# SparkFun_USB_LiPolyCharger_SingleCell.net
KiCad netlist of a schematic drawn in EAGLE
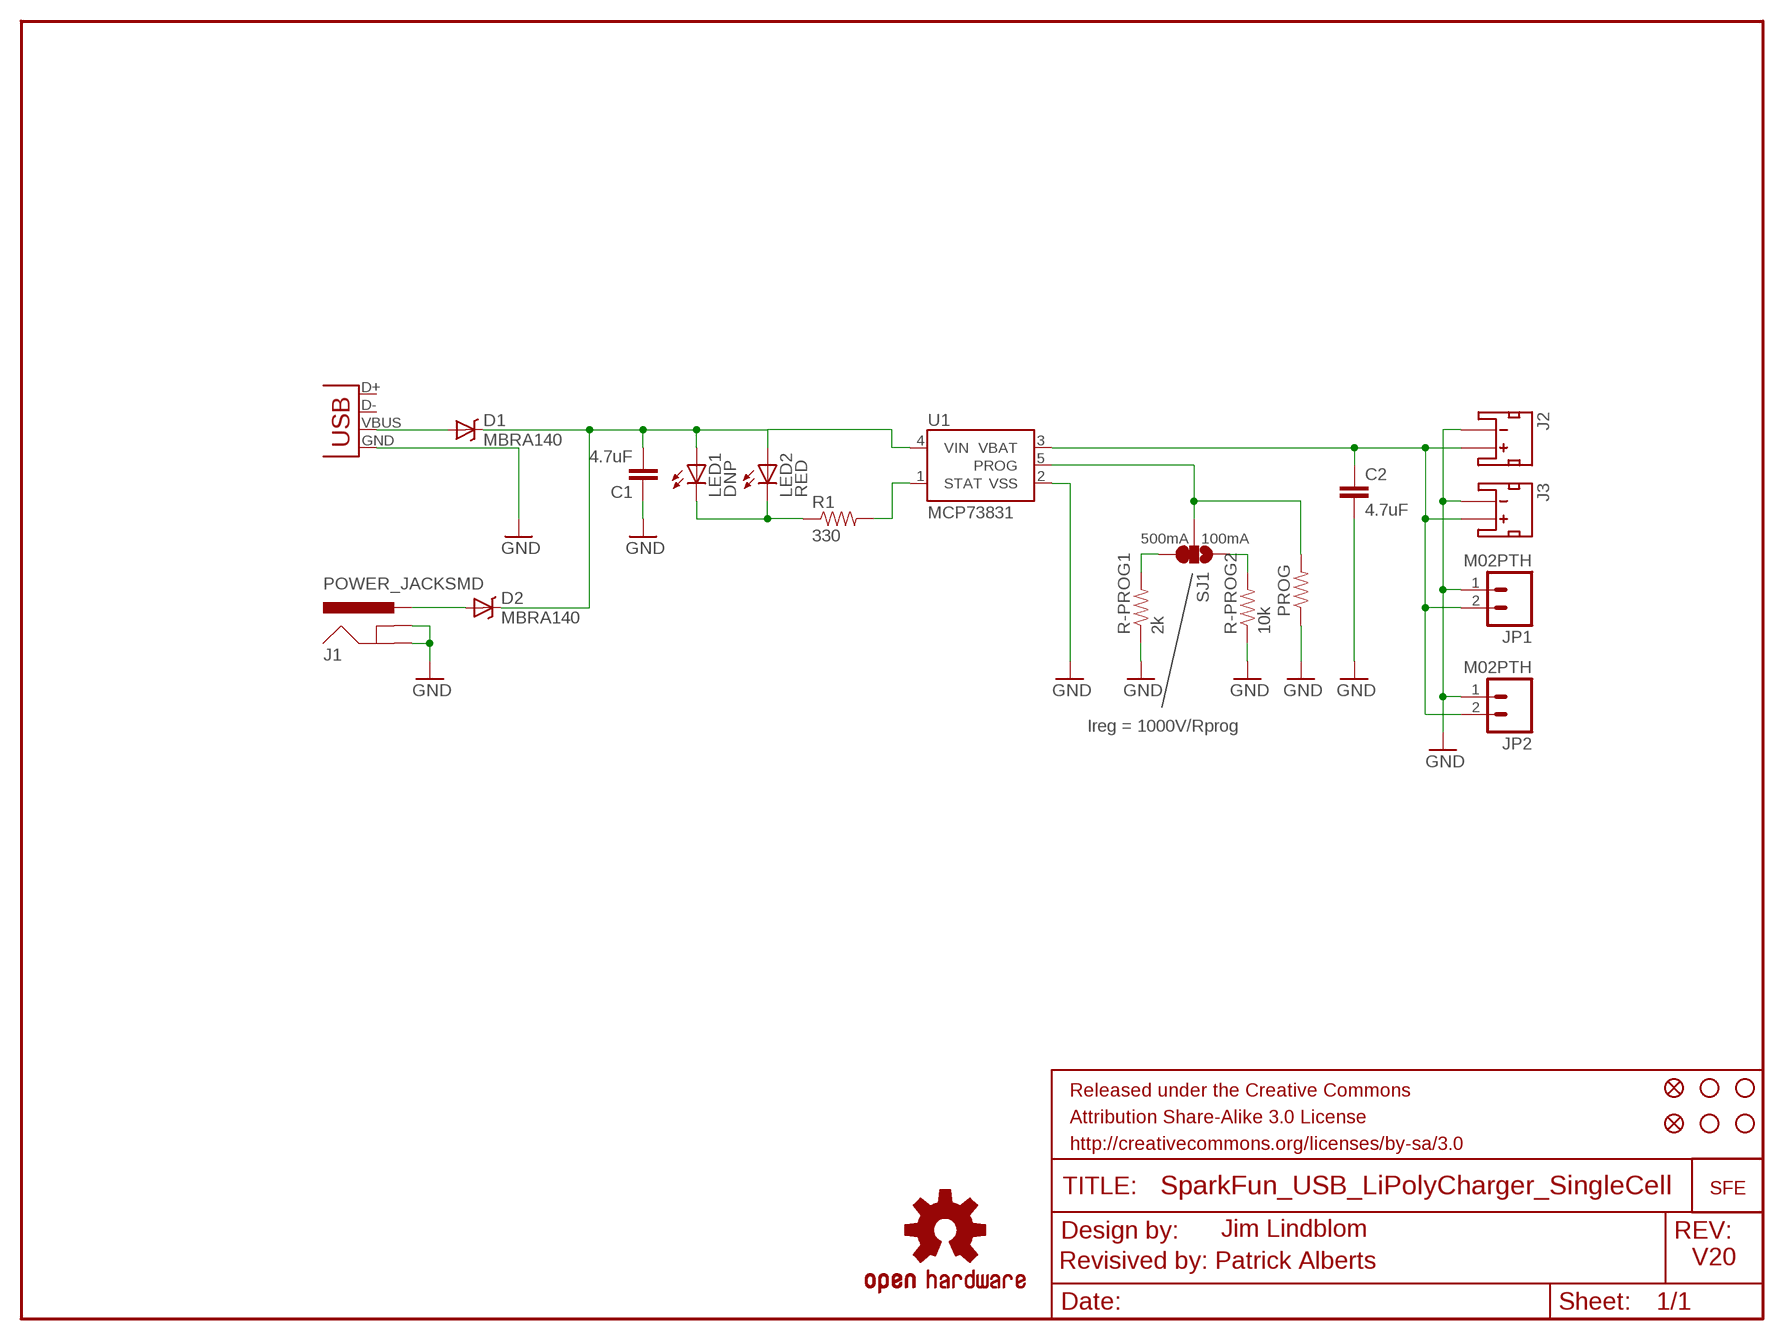
[diagram p0: schematic, sheet 1]

(export (version "E")
  (design (tool "Eeschema 10.0.6"))
  (components
    (comp (ref "C1")
      (value "4.7uF")
      (footprint "eagle-import:0603-CAP")
      (libsource (lib "eagle-import") (part "4.7UF-6.3V-10%(0603)0603"))
    )
    (comp (ref "C2")
      (value "4.7uF")
      (footprint "eagle-import:0603-CAP")
      (libsource (lib "eagle-import") (part "4.7UF-6.3V-10%(0603)0603"))
    )
    (comp (ref "D1")
      (value "MBRA140")
      (footprint "eagle-import:SMA-DIODE")
      (libsource (lib "eagle-import") (part "MBRA140"))
    )
    (comp (ref "D2")
      (value "MBRA140")
      (footprint "eagle-import:SMA-DIODE")
      (libsource (lib "eagle-import") (part "MBRA140"))
    )
    (comp (ref "FRAME1")
      (value "FRAME-LETTER")
      (footprint "eagle-import:CREATIVE_COMMONS")
      (libsource (lib "eagle-import") (part "FRAME-LETTER"))
    )
    (comp (ref "J1")
      (value "POWER_JACKSMD")
      (footprint "eagle-import:POWER_JACK_SMD")
      (libsource (lib "eagle-import") (part "POWER_JACKSMD"))
    )
    (comp (ref "J2")
      (value "JST_2MM_MALE")
      (footprint "eagle-import:JST-2-SMD")
      (libsource (lib "eagle-import") (part "JST_2MM_MALE"))
    )
    (comp (ref "J3")
      (value "JST_2MM_MALE")
      (footprint "eagle-import:JST-2-SMD")
      (libsource (lib "eagle-import") (part "JST_2MM_MALE"))
    )
    (comp (ref "JP1")
      (value "M02PTH")
      (footprint "eagle-import:1X02")
      (libsource (lib "eagle-import") (part "M02PTH"))
    )
    (comp (ref "JP2")
      (value "M02PTH")
      (footprint "eagle-import:1X02")
      (libsource (lib "eagle-import") (part "M02PTH"))
    )
    (comp (ref "JP7")
      (value "STAND-OFF")
      (footprint "eagle-import:STAND-OFF")
      (libsource (lib "eagle-import") (part "STAND-OFF"))
    )
    (comp (ref "JP8")
      (value "STAND-OFF")
      (footprint "eagle-import:STAND-OFF")
      (libsource (lib "eagle-import") (part "STAND-OFF"))
    )
    (comp (ref "JP9")
      (value "STAND-OFF")
      (footprint "eagle-import:STAND-OFF")
      (libsource (lib "eagle-import") (part "STAND-OFF"))
    )
    (comp (ref "JP10")
      (value "STAND-OFF")
      (footprint "eagle-import:STAND-OFF")
      (libsource (lib "eagle-import") (part "STAND-OFF"))
    )
    (comp (ref "JP11")
      (value "LOGO-SFENEW")
      (footprint "eagle-import:SFE-NEW-WEBLOGO")
      (libsource (lib "eagle-import") (part "LOGO-SFENEW"))
    )
    (comp (ref "JP12")
      (value "FIDUCIAL1X2")
      (footprint "eagle-import:FIDUCIAL-1X2")
      (libsource (lib "eagle-import") (part "FIDUCIAL1X2"))
    )
    (comp (ref "JP13")
      (value "FIDUCIAL1X2")
      (footprint "eagle-import:FIDUCIAL-1X2")
      (libsource (lib "eagle-import") (part "FIDUCIAL1X2"))
    )
    (comp (ref "LED1")
      (value "DNP")
      (footprint "eagle-import:LED3MM")
      (libsource (lib "eagle-import") (part "LED3MM"))
    )
    (comp (ref "LED2")
      (value "RED")
      (footprint "eagle-import:LED-0603")
      (libsource (lib "eagle-import") (part "LED-RED0603"))
    )
    (comp (ref "LOGO1")
      (value "OSHW-LOGOS")
      (footprint "eagle-import:OSHW-LOGO-S")
      (libsource (lib "eagle-import") (part "OSHW-LOGOS"))
    )
    (comp (ref "PROG")
      (value "RESISTORAXIAL-0.3")
      (footprint "eagle-import:AXIAL-0.3")
      (libsource (lib "eagle-import") (part "RESISTORAXIAL-0.3"))
    )
    (comp (ref "R-PROG1")
      (value "2k")
      (footprint "eagle-import:0603-RES")
      (libsource (lib "eagle-import") (part "2.0KOHM1/10W5%(0603)"))
    )
    (comp (ref "R-PROG2")
      (value "10k")
      (footprint "eagle-import:0603-RES")
      (libsource (lib "eagle-import") (part "10KOHM1/10W1%(0603)0603"))
    )
    (comp (ref "R1")
      (value "330")
      (footprint "eagle-import:0603-RES")
      (libsource (lib "eagle-import") (part "330OHM1/10W1%(0603)"))
    )
    (comp (ref "SJ1")
      (value "SOLDERJUMPER_2WAYS")
      (footprint "eagle-import:SJ_3")
      (libsource (lib "eagle-import") (part "SOLDERJUMPER_2WAYS"))
    )
    (comp (ref "U1")
      (value "MCP73831")
      (footprint "eagle-import:SOT23-5")
      (libsource (lib "eagle-import") (part "MCP73831"))
    )
    (comp (ref "X1")
      (value "USBSMD")
      (footprint "eagle-import:USB-MINIB")
      (libsource (lib "eagle-import") (part "USBSMD"))
    )
  )
  (nets
    (net (code "1") (name "GND") (class "Default")
      (node (ref "C1") (pin "1") (pinfunction "1_1") (pintype "passive"))
      (node (ref "C2") (pin "2") (pinfunction "2_2") (pintype "passive"))
      (node (ref "J1") (pin "GND") (pinfunction "GNDBREAK_GND") (pintype "bidirectional"))
      (node (ref "J1") (pin "P$4") (pinfunction "GND_P$4") (pintype "bidirectional"))
      (node (ref "J2") (pin "1") (pinfunction "-_1") (pintype "bidirectional"))
      (node (ref "J3") (pin "1") (pinfunction "-_1") (pintype "bidirectional"))
      (node (ref "JP1") (pin "1") (pinfunction "1_1") (pintype "passive"))
      (node (ref "JP2") (pin "1") (pinfunction "1_1") (pintype "passive"))
      (node (ref "PROG") (pin "P$1") (pinfunction "1_P$1") (pintype "passive"))
      (node (ref "R-PROG1") (pin "1") (pinfunction "1_1") (pintype "passive"))
      (node (ref "R-PROG2") (pin "1") (pinfunction "1_1") (pintype "passive"))
      (node (ref "U1") (pin "2") (pinfunction "VSS_2") (pintype "power_in"))
      (node (ref "X1") (pin "GND") (pinfunction "GND_GND") (pintype "bidirectional"))
    )
    (net (code "2") (name "Net-(D1-PadA)") (class "Default")
      (node (ref "D1") (pin "A") (pinfunction "A_A") (pintype "passive"))
      (node (ref "X1") (pin "VBUS") (pinfunction "VBUS_VBUS") (pintype "bidirectional"))
    )
    (net (code "3") (name "Net-(J1-PWR)") (class "Default")
      (node (ref "D2") (pin "A") (pinfunction "A_A") (pintype "passive"))
      (node (ref "J1") (pin "VIN0") (pinfunction "PWR_VIN0") (pintype "bidirectional"))
    )
    (net (code "4") (name "Net-(J2-+)") (class "Default")
      (node (ref "C2") (pin "1") (pinfunction "1_1") (pintype "passive"))
      (node (ref "J2") (pin "2") (pinfunction "+_2") (pintype "bidirectional"))
      (node (ref "J3") (pin "2") (pinfunction "+_2") (pintype "bidirectional"))
      (node (ref "JP1") (pin "2") (pinfunction "2_2") (pintype "passive"))
      (node (ref "JP2") (pin "2") (pinfunction "2_2") (pintype "passive"))
      (node (ref "U1") (pin "3") (pinfunction "VBAT_3") (pintype "power_in"))
    )
    (net (code "5") (name "Net-(LED1-C)") (class "Default")
      (node (ref "LED1") (pin "K") (pinfunction "C_K") (pintype "passive"))
      (node (ref "LED2") (pin "C") (pinfunction "C_C") (pintype "passive"))
      (node (ref "R1") (pin "1") (pinfunction "1_1") (pintype "passive"))
    )
    (net (code "6") (name "Net-(PROG-2)") (class "Default")
      (node (ref "PROG") (pin "P$2") (pinfunction "2_P$2") (pintype "passive"))
      (node (ref "SJ1") (pin "2") (pinfunction "2_2") (pintype "passive"))
      (node (ref "U1") (pin "5") (pinfunction "PROG_5") (pintype "input"))
    )
    (net (code "7") (name "Net-(R-PROG1-Pad2)") (class "Default")
      (node (ref "R-PROG1") (pin "2") (pinfunction "2_2") (pintype "passive"))
      (node (ref "SJ1") (pin "3") (pinfunction "3_3") (pintype "passive"))
    )
    (net (code "8") (name "Net-(R-PROG2-Pad2)") (class "Default")
      (node (ref "R-PROG2") (pin "2") (pinfunction "2_2") (pintype "passive"))
      (node (ref "SJ1") (pin "1") (pinfunction "1_1") (pintype "passive"))
    )
    (net (code "9") (name "Net-(U1-STAT)") (class "Default")
      (node (ref "R1") (pin "2") (pinfunction "2_2") (pintype "passive"))
      (node (ref "U1") (pin "1") (pinfunction "STAT_1") (pintype "output"))
    )
    (net (code "10") (name "Net-(U1-VIN)") (class "Default")
      (node (ref "C1") (pin "2") (pinfunction "2_2") (pintype "passive"))
      (node (ref "D1") (pin "C") (pinfunction "C_C") (pintype "passive"))
      (node (ref "D2") (pin "C") (pinfunction "C_C") (pintype "passive"))
      (node (ref "LED1") (pin "A") (pinfunction "A_A") (pintype "passive"))
      (node (ref "LED2") (pin "A") (pinfunction "A_A") (pintype "passive"))
      (node (ref "U1") (pin "4") (pinfunction "VIN_4") (pintype "power_in"))
    )
    (net (code "11") (name "unconnected-(J2-PAD1-PadNC1)") (class "Default")
      (node (ref "J2") (pin "NC1") (pinfunction "PAD1_NC1") (pintype "bidirectional"))
    )
    (net (code "12") (name "unconnected-(J2-PAD2-PadNC2)") (class "Default")
      (node (ref "J2") (pin "NC2") (pinfunction "PAD2_NC2") (pintype "bidirectional"))
    )
    (net (code "13") (name "unconnected-(J3-PAD1-PadNC1)") (class "Default")
      (node (ref "J3") (pin "NC1") (pinfunction "PAD1_NC1") (pintype "bidirectional"))
    )
    (net (code "14") (name "unconnected-(J3-PAD2-PadNC2)") (class "Default")
      (node (ref "J3") (pin "NC2") (pinfunction "PAD2_NC2") (pintype "bidirectional"))
    )
    (net (code "15") (name "unconnected-(X1-PadD+)") (class "Default")
      (node (ref "X1") (pin "D+") (pinfunction "D+_D+") (pintype "bidirectional"))
    )
    (net (code "16") (name "unconnected-(X1-PadD-)") (class "Default")
      (node (ref "X1") (pin "D-") (pinfunction "D-_D-") (pintype "bidirectional"))
    )
  )
)
